# 12V_Buck.net
KiCad netlist of a schematic drawn in Altium Designer
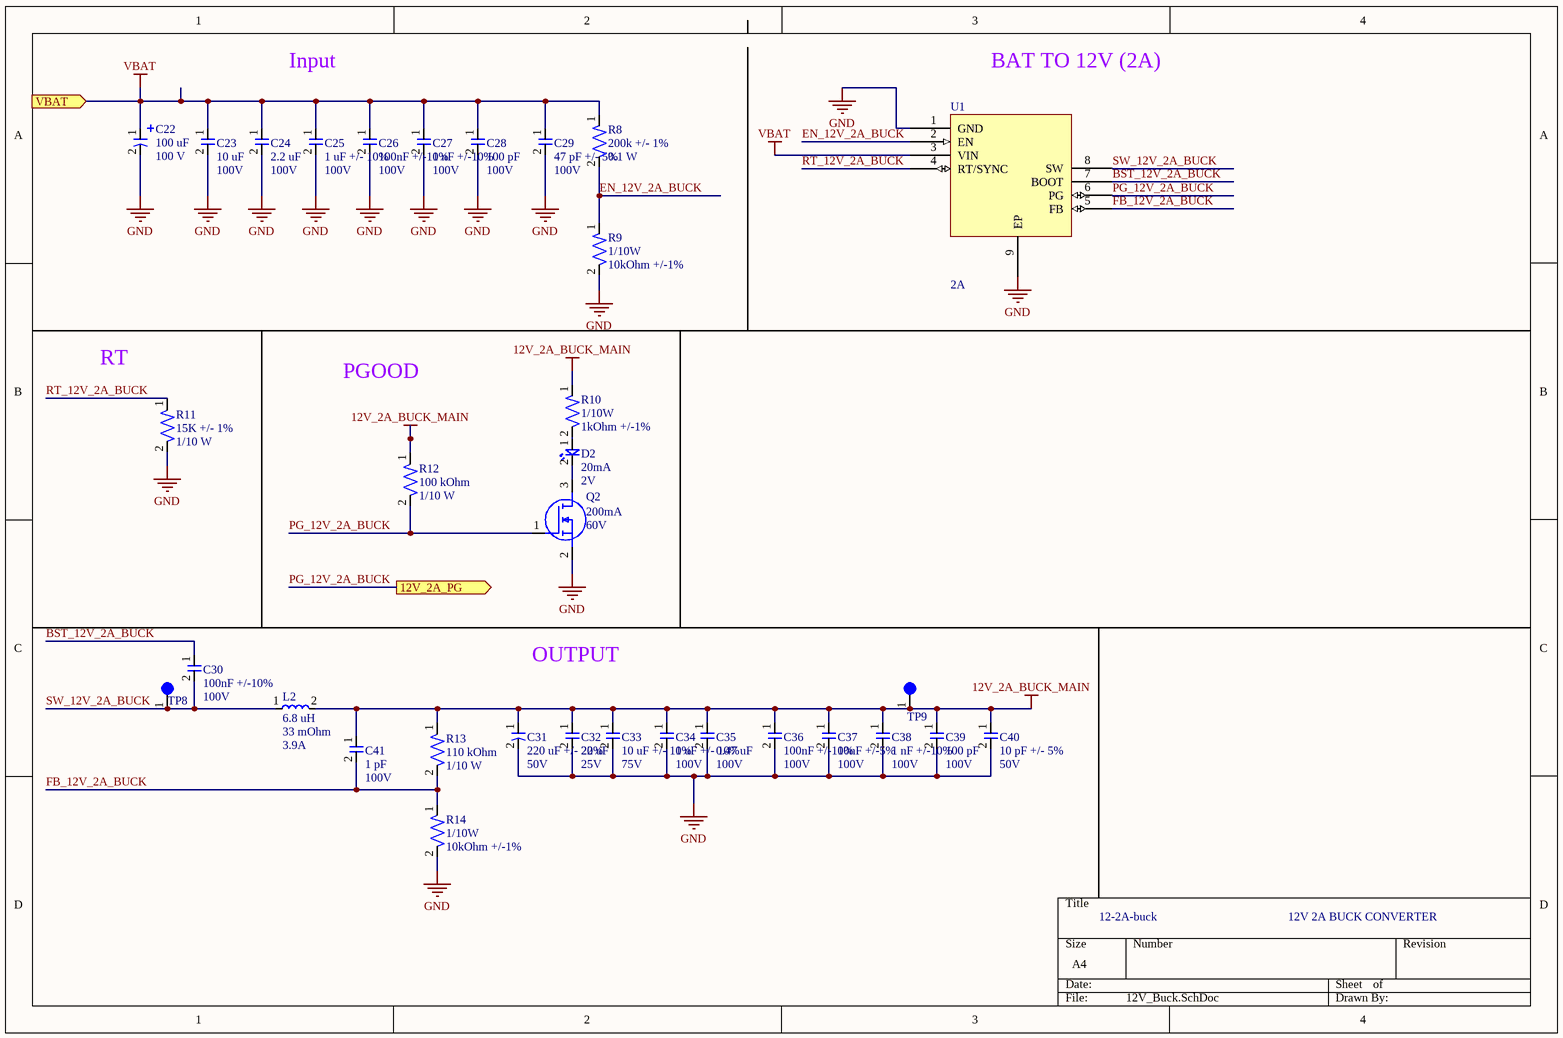
[diagram p0: 12V_Buck.SchDoc]

(export (version "E")
  (design (tool "Eeschema 10.0.6"))
  (components
    (comp (ref "C22")
      (value "100SEV100M12.5X16")
      (footprint "ELEC-100U-0001")
      (description "100 µF 100 V Aluminum Electrolytic Capacitors Radial, Can - SMD 2000 Hrs @ 85°C")
      (fields
        (field (name "MANUFACTURER") "Rubycon")
        (field (name "TOLERANCE") "+/- 20%")
        (field (name "CAPACITANCE") "100 uF")
        (field (name "VOLTAGE") "100 V")
      )
      (libsource (lib "MasterLib") (part "ELEC-100U-0001"))
    )
    (comp (ref "C23")
      (value "GRM32EC72A106KE05L")
      (footprint "CAP-1210")
      (description "10 µF ±10% 100V Ceramic Capacitor X7S 1210 (3225 Metric)")
      (fields (field (name "CAPCITANCE") "10 uF") (field (name "VOLTAGE RATING") "100V"))
      (libsource (lib "MasterLib") (part "CAP-10U-0003"))
    )
    (comp (ref "C24")
      (value "CL31B225KCHSNNE")
      (footprint "CAP-1206")
      (description "2.2 µF ±10% 100V Ceramic Capacitor X7R 1206 (3216 Metric)")
      (fields
        (field (name "MANUFACTURER") "Samsung Electro-Mechanics")
        (field (name "TOLERANCE") "+/- 10%")
        (field (name "CAPACITANCE") "2.2 uF")
        (field (name "VOLTAGE") "100V")
      )
      (libsource (lib "MasterLib") (part "CAP-2.2U-0003"))
    )
    (comp (ref "C25")
      (value "CL31B105KCHNNNE")
      (footprint "CAP-1206 - duplicate")
      (description "1 µF ±10% 100V Ceramic Capacitor X7R 1206 (3216 Metric)")
      (fields (field (name "CAPACITANCE") "1 uF +/- 10%") (field (name "VOLTAGE") "100V"))
      (libsource (lib "MasterLib") (part "CAP-1U-0001"))
    )
    (comp (ref "C26")
      (value "CC0603KRX7R0BB104")
      (footprint "CAP-0603")
      (description "CAP CER 0.1UF 100V X7R 0603")
      (fields
        (field (name "MANUFACTURER") "YAGEO")
        (field (name "CAPACITANCE") "100nF +/-10%")
        (field (name "VOLTAGE RATING") "100V")
      )
      (libsource (lib "MasterLib") (part "CAP-100N-0001"))
    )
    (comp (ref "C27")
      (value "C0603Y102K1RAC7867")
      (footprint "CAP-0603")
      (description "1000 pF ±10% 100V Ceramic Capacitor X7R 0603 (1608 Metric)")
      (fields (field (name "CAPACITANCE") "1 nF +/-10%") (field (name "VOLTAGE") "100V"))
      (libsource (lib "MasterLib") (part "CAP-1N-0001"))
    )
    (comp (ref "C28")
      (value "0603N101J101CT")
      (footprint "CAP-0603")
      (description "100 pF ±5% 100V Ceramic Capacitor C0G, NP0 0603 (1608 Metric)")
      (fields
        (field (name "TOLERANCE") "+/-5%")
        (field (name "CAPACITANCE") "100 pF")
        (field (name "VOLTAGE") "100V")
      )
      (libsource (lib "MasterLib") (part "CAP-100P-0002"))
    )
    (comp (ref "C29")
      (value "7447798111")
      (footprint "CAP-0603")
      (description "47 pF ±5% 100V Ceramic Capacitor C0G, NP0 0603 (1608 Metric)")
      (fields (field (name "CAPACITANCE") "47 pF +/- 5%") (field (name "VOLTAGE RATING") "100V"))
      (libsource (lib "MasterLib") (part "CAP-47P-0001"))
    )
    (comp (ref "C30")
      (value "CC0603KRX7R0BB104")
      (footprint "CAP-0603")
      (description "CAP CER 0.1UF 100V X7R 0603")
      (fields
        (field (name "MANUFACTURER") "YAGEO")
        (field (name "CAPACITANCE") "100nF +/-10%")
        (field (name "VOLTAGE RATING") "100V")
      )
      (libsource (lib "MasterLib") (part "CAP-100N-0001"))
    )
    (comp (ref "C31")
      (value "50TZV220M10X10.5")
      (footprint "ELEC-220U-0003")
      (description "220 µF 50 V Aluminum Electrolytic Capacitors Radial, Can - SMD 2000 Hrs @ 105°C")
      (fields (field (name "CAPACITANCE") "220 uF +/- 20%") (field (name "VOLTAGE RATING") "50V"))
      (libsource (lib "MasterLib") (part "ELEC-220U-0003"))
    )
    (comp (ref "C32")
      (value "CL32B226KAJNNNE")
      (footprint "CAP-1210")
      (description "22 µF ±10% 25V Ceramic Capacitor X7R 1210 (3225 Metric)")
      (fields
        (field (name "TOLERANCE") "+/- 10%")
        (field (name "CAPACITANCE") "22 uF")
        (field (name "VOLTAGE") "25V")
      )
      (libsource (lib "MasterLib") (part "CAP-22U-0003"))
    )
    (comp (ref "C33")
      (value "C3225X7R1N106K250AC")
      (footprint "CAP-1210")
      (description "10 µF ±10% 75V Ceramic Capacitor X7R 1210 (3225 Metric)")
      (fields (field (name "CAPACITANCE") "10 uF +/- 10%") (field (name "VOLTAGE RATING") "75V"))
      (libsource (lib "MasterLib") (part "CAP-10U-0004"))
    )
    (comp (ref "C34")
      (value "CL31B105KCHNNNE")
      (footprint "CAP-1206 - duplicate")
      (description "1 µF ±10% 100V Ceramic Capacitor X7R 1206 (3216 Metric)")
      (fields (field (name "CAPACITANCE") "1 uF +/- 10%") (field (name "VOLTAGE") "100V"))
      (libsource (lib "MasterLib") (part "CAP-1U-0001"))
    )
    (comp (ref "C35")
      (value "KAM21KR72A474KL")
      (footprint "CAP-0805")
      (description "0.47 µF ±10% 100V Ceramic Capacitor X7R 0805 (2012 Metric)")
      (fields
        (field (name "TOLERANCE") "+/- 10%")
        (field (name "CAPACITANCE") "0.47 uF")
        (field (name "VOLTAGE") "100V")
      )
      (libsource (lib "MasterLib") (part "CAP-0.47U-0001"))
    )
    (comp (ref "C36")
      (value "CC0603KRX7R0BB104")
      (footprint "CAP-0603")
      (description "CAP CER 0.1UF 100V X7R 0603")
      (fields
        (field (name "MANUFACTURER") "YAGEO")
        (field (name "CAPACITANCE") "100nF +/-10%")
        (field (name "VOLTAGE RATING") "100V")
      )
      (libsource (lib "MasterLib") (part "CAP-100N-0001"))
    )
    (comp (ref "C37")
      (value "C1608C0G2A103J080AC")
      (footprint "CAP-0603")
      (description "CAP CER 10000PF 100V C0G 0603")
      (fields
        (field (name "MANUFACTURER") "TDK Corporation")
        (field (name "CAPACITANCE") "10nF +/-5%")
        (field (name "VOLTAGE RATING") "100V")
      )
      (libsource (lib "MasterLib") (part "CAP-10N-0002"))
    )
    (comp (ref "C38")
      (value "C0603Y102K1RAC7867")
      (footprint "CAP-0603")
      (description "1000 pF ±10% 100V Ceramic Capacitor X7R 0603 (1608 Metric)")
      (fields (field (name "CAPACITANCE") "1 nF +/-10%") (field (name "VOLTAGE") "100V"))
      (libsource (lib "MasterLib") (part "CAP-1N-0001"))
    )
    (comp (ref "C39")
      (value "0603N101J101CT")
      (footprint "CAP-0603")
      (description "100 pF ±5% 100V Ceramic Capacitor C0G, NP0 0603 (1608 Metric)")
      (fields
        (field (name "TOLERANCE") "+/-5%")
        (field (name "CAPACITANCE") "100 pF")
        (field (name "VOLTAGE") "100V")
      )
      (libsource (lib "MasterLib") (part "CAP-100P-0002"))
    )
    (comp (ref "C40")
      (value "0603N100J500CT")
      (footprint "CAP-0603")
      (description "10 pF ±5% 50V Ceramic Capacitor C0G, NP0 0603 (1608 Metric)")
      (fields
        (field (name "MANUFACTURER") "Walshin Technology Corporation")
        (field (name "CAPACITANCE") "10 pF +/- 5%")
        (field (name "VOLTAGE RATING") "50V")
      )
      (libsource (lib "MasterLib") (part "CAP-10P-0001"))
    )
    (comp (ref "C41")
      (value "885012006087")
      (footprint "CAP-0603")
      (description "1 pF ±0.25pF 100V Ceramic Capacitor C0G, NP0 0603 (1608 Metric)")
      (fields
        (field (name "TOLERANCE") "+/- 0.25 pF")
        (field (name "CAPACITANCE") "1 pF")
        (field (name "VOLTAGE") "100V")
      )
      (libsource (lib "MasterLib") (part "CAP-1P-0001"))
    )
    (comp (ref "D2")
      (value "150060AS75000")
      (footprint "LED-0603")
      (description "CAP CER 0.1UF 100V X7R 0603")
      (fields
        (field (name "MANUFACTURER") "Wurth Electronik")
        (field (name "CURRENT RATING") "20mA")
        (field (name "VF") "2V")
      )
      (libsource (lib "MasterLib") (part "LED_Amber_0001"))
    )
    (comp (ref "L2")
      (value "SRN8040-6R8Y")
      (footprint "PWRIND-6.8U-0001")
      (description "6.8 µH Semi-Shielded Drum Core, Wirewound Inductor 3.9 A 33mOhm Max Nonstandard")
      (fields
        (field (name "TOLERANCE") "30%")
        (field (name "INDUCTANCE") "6.8 uH")
        (field (name "DCR") "33 mOhm")
        (field (name "DCI") "3.9A")
      )
      (libsource (lib "MasterLib") (part "PWRIND-6.8U-0001"))
    )
    (comp (ref "Q2")
      (value "T2N7002AK,LM")
      (footprint "NMOS-SOT23-3")
      (description "MOSFET N-CH 60V 200MA SOT23")
      (fields
        (field (name "MANUFACTURER") "Toshiba")
        (field (name "ID-CONTINUOUS") "200mA")
        (field (name "VDS-MAX") "60V")
      )
      (libsource (lib "MasterLib") (part "NMOS-200MA-0001"))
    )
    (comp (ref "R8")
      (value "ERJ-3EKF2003V")
      (footprint "RES-0603")
      (description "200 kOhms ±1% 0.1W, 1/10W Chip Resistor 0603 (1608 Metric) Automotive AEC-Q200 Thick Film")
      (fields
        (field (name "MANUFACTURER") "Panasonic Electronic Components")
        (field (name "RESISTANCE") "200k +/- 1%")
        (field (name "POWER RATING") "0.1 W")
      )
      (libsource (lib "MasterLib") (part "RES-200K-0001"))
    )
    (comp (ref "R9")
      (value "RC0603FR-0710KP")
      (footprint "RES-0603")
      (description "RES SMD 10K OHM 1% 1/10W 0603")
      (fields
        (field (name "MANUFACTURER") "YAGEO")
        (field (name "POWER RATING") "1/10W")
        (field (name "RESISTANCE") "10kOhm +/-1%")
      )
      (libsource (lib "MasterLib") (part "RES-10K-0002"))
    )
    (comp (ref "R10")
      (value "RT0603FRE131KL")
      (footprint "RES-0603")
      (description "1 kOhms ±1% 0.1W, 1/10W Chip Resistor 0603 (1608 Metric) Thin Film")
      (fields
        (field (name "MANUFACTURER") "YAGEO")
        (field (name "POWER RATING") "1/10W")
        (field (name "RESISTANCE") "1kOhm +/-1%")
      )
      (libsource (lib "MasterLib") (part "RES-1K-0002"))
    )
    (comp (ref "R11")
      (value "ERJ-2RKF1502X")
      (footprint "RES-0402")
      (description "15 kOhms ±1% 0.1W, 1/10W Chip Resistor 0402 (1005 Metric) Automotive AEC-Q200 Thick Film")
      (fields (field (name "RES") "15K +/- 1%") (field (name "POWER") "1/10 W"))
      (libsource (lib "MasterLib") (part "RES-15K-0001"))
    )
    (comp (ref "R12")
      (value "RC0603FR-07100KL")
      (footprint "RES-0603")
      (description "100 kOhms ±1% 0.1W, 1/10W Chip Resistor 0603 (1608 Metric) Moisture Resistant Thick Film")
      (fields
        (field (name "TOLERANCE") "+/- 1%")
        (field (name "RESISTANCE") "100 kOhm")
        (field (name "POWER") "1/10 W")
      )
      (libsource (lib "MasterLib") (part "RES-100K-0003"))
    )
    (comp (ref "R13")
      (value "RC0603FR-07110KL")
      (footprint "RES-0603")
      (description "110 kOhms ±1% 0.1W, 1/10W Chip Resistor 0603 (1608 Metric) Moisture Resistant Thick Film")
      (fields
        (field (name "TOLERANCE") "+/- 1%")
        (field (name "RESISTANCE") "110 kOhm")
        (field (name "POWER") "1/10 W")
      )
      (libsource (lib "MasterLib") (part "RES-110K-0001"))
    )
    (comp (ref "R14")
      (value "RC0603FR-0710KP")
      (footprint "RES-0603")
      (description "RES SMD 10K OHM 1% 1/10W 0603")
      (fields
        (field (name "MANUFACTURER") "YAGEO")
        (field (name "POWER RATING") "1/10W")
        (field (name "RESISTANCE") "10kOhm +/-1%")
      )
      (libsource (lib "MasterLib") (part "RES-10K-0002"))
    )
    (comp (ref "TP8")
      (value "5003")
      (footprint "TEST-POINT-0001")
      (description "Oranange PC Test Point, Miniature Phoisphor Bronze Silver Plating Through Hole Mounting Type")
      (libsource (lib "MasterLib") (part "TEST-POINT-0001"))
    )
    (comp (ref "TP9")
      (value "5003")
      (footprint "TEST-POINT-0001")
      (description "Oranange PC Test Point, Miniature Phoisphor Bronze Silver Plating Through Hole Mounting Type")
      (libsource (lib "MasterLib") (part "TEST-POINT-0001"))
    )
    (comp (ref "U1")
      (value "LMR38020SDDAR")
      (footprint "IC-8PowerSOIC")
      (description "Buck Switching Regulator IC Positive Adjustable 1V 1 Output 2A 8-PowerSOIC (0.154\", 3.90mm Width)")
      (fields (field (name "CURRENT") "2A"))
      (libsource (lib "MasterLib") (part "IC-BUCK-0007"))
    )
  )
  (nets
    (net (code "1") (name "/BST_12V_2A_BUCK") (class "Default")
      (node (ref "C30") (pin "1") (pinfunction "1_1") (pintype "passive"))
      (node (ref "U1") (pin "7") (pinfunction "BOOT_7") (pintype "power_in"))
    )
    (net (code "2") (name "/EN_12V_2A_BUCK") (class "Default")
      (node (ref "R8") (pin "2") (pinfunction "2_2") (pintype "passive"))
      (node (ref "R9") (pin "1") (pinfunction "1_1") (pintype "passive"))
      (node (ref "U1") (pin "2") (pinfunction "EN_2") (pintype "input"))
    )
    (net (code "3") (name "/FB_12V_2A_BUCK") (class "Default")
      (node (ref "C41") (pin "2") (pinfunction "2_2") (pintype "passive"))
      (node (ref "R13") (pin "2") (pinfunction "2_2") (pintype "passive"))
      (node (ref "R14") (pin "1") (pinfunction "1_1") (pintype "passive"))
      (node (ref "U1") (pin "5") (pinfunction "FB_5") (pintype "bidirectional"))
    )
    (net (code "4") (name "/PG_12V_2A_BUCK") (class "Default")
      (node (ref "Q2") (pin "1") (pinfunction "G_1") (pintype "passive"))
      (node (ref "R12") (pin "2") (pinfunction "2_2") (pintype "passive"))
      (node (ref "U1") (pin "6") (pinfunction "PG_6") (pintype "bidirectional"))
    )
    (net (code "5") (name "/RT_12V_2A_BUCK") (class "Default")
      (node (ref "R11") (pin "1") (pinfunction "1_1") (pintype "passive"))
      (node (ref "U1") (pin "4") (pinfunction "RT/SYNC_4") (pintype "bidirectional"))
    )
    (net (code "6") (name "/SW_12V_2A_BUCK") (class "Default")
      (node (ref "C30") (pin "2") (pinfunction "2_2") (pintype "passive"))
      (node (ref "L2") (pin "1") (pinfunction "1_1") (pintype "passive"))
      (node (ref "TP8") (pin "1") (pinfunction "0_1") (pintype "passive"))
      (node (ref "U1") (pin "8") (pinfunction "SW_8") (pintype "power_in"))
    )
    (net (code "7") (name "12V_2A_BUCK_MAIN") (class "Default")
      (node (ref "C31") (pin "1") (pinfunction "1_1") (pintype "passive"))
      (node (ref "C32") (pin "1") (pinfunction "1_1") (pintype "passive"))
      (node (ref "C33") (pin "1") (pinfunction "1_1") (pintype "passive"))
      (node (ref "C34") (pin "1") (pinfunction "1_1") (pintype "passive"))
      (node (ref "C35") (pin "1") (pinfunction "1_1") (pintype "passive"))
      (node (ref "C36") (pin "1") (pinfunction "1_1") (pintype "passive"))
      (node (ref "C37") (pin "1") (pinfunction "1_1") (pintype "passive"))
      (node (ref "C38") (pin "1") (pinfunction "1_1") (pintype "passive"))
      (node (ref "C39") (pin "1") (pinfunction "1_1") (pintype "passive"))
      (node (ref "C40") (pin "1") (pinfunction "1_1") (pintype "passive"))
      (node (ref "C41") (pin "1") (pinfunction "1_1") (pintype "passive"))
      (node (ref "L2") (pin "2") (pinfunction "2_2") (pintype "passive"))
      (node (ref "R10") (pin "1") (pinfunction "1_1") (pintype "passive"))
      (node (ref "R12") (pin "1") (pinfunction "1_1") (pintype "passive"))
      (node (ref "R13") (pin "1") (pinfunction "1_1") (pintype "passive"))
      (node (ref "TP9") (pin "1") (pinfunction "0_1") (pintype "passive"))
    )
    (net (code "8") (name "GND") (class "Default")
      (node (ref "C22") (pin "2") (pinfunction "2_2") (pintype "passive"))
      (node (ref "C23") (pin "2") (pinfunction "2_2") (pintype "passive"))
      (node (ref "C24") (pin "2") (pinfunction "2_2") (pintype "passive"))
      (node (ref "C25") (pin "2") (pinfunction "2_2") (pintype "passive"))
      (node (ref "C26") (pin "2") (pinfunction "2_2") (pintype "passive"))
      (node (ref "C27") (pin "2") (pinfunction "2_2") (pintype "passive"))
      (node (ref "C28") (pin "2") (pinfunction "2_2") (pintype "passive"))
      (node (ref "C29") (pin "2") (pinfunction "2_2") (pintype "passive"))
      (node (ref "C31") (pin "2") (pinfunction "2_2") (pintype "passive"))
      (node (ref "C32") (pin "2") (pinfunction "2_2") (pintype "passive"))
      (node (ref "C33") (pin "2") (pinfunction "2_2") (pintype "passive"))
      (node (ref "C34") (pin "2") (pinfunction "2_2") (pintype "passive"))
      (node (ref "C35") (pin "2") (pinfunction "2_2") (pintype "passive"))
      (node (ref "C36") (pin "2") (pinfunction "2_2") (pintype "passive"))
      (node (ref "C37") (pin "2") (pinfunction "2_2") (pintype "passive"))
      (node (ref "C38") (pin "2") (pinfunction "2_2") (pintype "passive"))
      (node (ref "C39") (pin "2") (pinfunction "2_2") (pintype "passive"))
      (node (ref "C40") (pin "2") (pinfunction "2_2") (pintype "passive"))
      (node (ref "Q2") (pin "2") (pinfunction "S_2") (pintype "passive"))
      (node (ref "R11") (pin "2") (pinfunction "2_2") (pintype "passive"))
      (node (ref "R14") (pin "2") (pinfunction "2_2") (pintype "passive"))
      (node (ref "R9") (pin "2") (pinfunction "2_2") (pintype "passive"))
      (node (ref "U1") (pin "1") (pinfunction "GND_1") (pintype "power_in"))
      (node (ref "U1") (pin "9") (pinfunction "EP_9") (pintype "power_in"))
    )
    (net (code "9") (name "Net-(D2-Pad1)") (class "Default")
      (node (ref "D2") (pin "1") (pinfunction "1_1") (pintype "passive"))
      (node (ref "R10") (pin "2") (pinfunction "2_2") (pintype "passive"))
    )
    (net (code "10") (name "Net-(Q2-D)") (class "Default")
      (node (ref "D2") (pin "2") (pinfunction "2_2") (pintype "passive"))
      (node (ref "Q2") (pin "3") (pinfunction "D_3") (pintype "passive"))
    )
    (net (code "11") (name "VBAT") (class "Default")
      (node (ref "C22") (pin "1") (pinfunction "1_1") (pintype "passive"))
      (node (ref "C23") (pin "1") (pinfunction "1_1") (pintype "passive"))
      (node (ref "C24") (pin "1") (pinfunction "1_1") (pintype "passive"))
      (node (ref "C25") (pin "1") (pinfunction "1_1") (pintype "passive"))
      (node (ref "C26") (pin "1") (pinfunction "1_1") (pintype "passive"))
      (node (ref "C27") (pin "1") (pinfunction "1_1") (pintype "passive"))
      (node (ref "C28") (pin "1") (pinfunction "1_1") (pintype "passive"))
      (node (ref "C29") (pin "1") (pinfunction "1_1") (pintype "passive"))
      (node (ref "R8") (pin "1") (pinfunction "1_1") (pintype "passive"))
      (node (ref "U1") (pin "3") (pinfunction "VIN_3") (pintype "power_in"))
    )
  )
)
